# DrivePDU.net
KiCad netlist of a schematic drawn in EAGLE
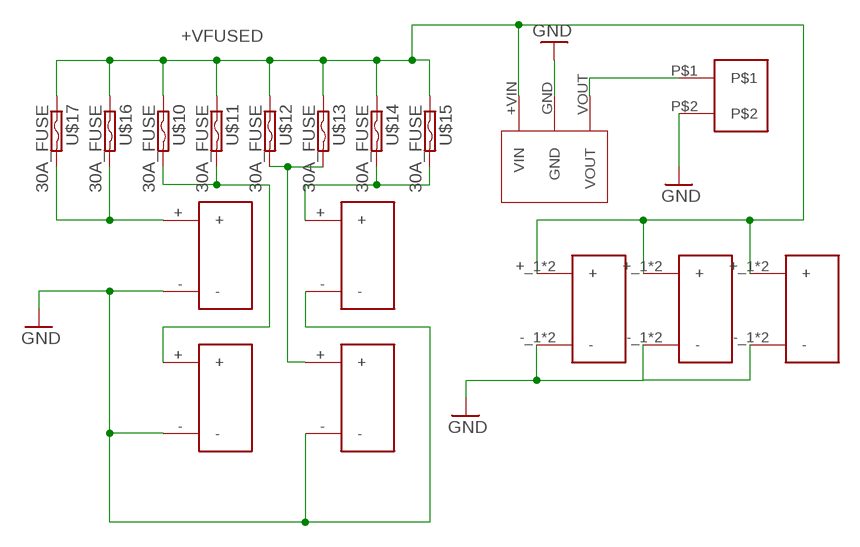
[diagram p0: schematic, sheet 1]

(export (version "E")
  (design (tool "Eeschema 10.0.6"))
  (components
    (comp (ref "U$1")
      (value "PP45_HOR_4GRD")
      (footprint "eagle-import:PP45_HOR_4GRD")
      (libsource (lib "eagle-import") (part "PP45_HOR_4GRD"))
    )
    (comp (ref "U$2")
      (value "PP45_HOR_4GRD")
      (footprint "eagle-import:PP45_HOR_4GRD")
      (libsource (lib "eagle-import") (part "PP45_HOR_4GRD"))
    )
    (comp (ref "U$3")
      (value "PP45_HOR_4GRD")
      (footprint "eagle-import:PP45_HOR_4GRD")
      (libsource (lib "eagle-import") (part "PP45_HOR_4GRD"))
    )
    (comp (ref "U$4")
      (value "PP45_HOR_2BOT")
      (footprint "eagle-import:PP45_HOR_2BOT")
      (libsource (lib "eagle-import") (part "PP45_HOR_2BOT"))
    )
    (comp (ref "U$5")
      (value "PP45_HOR_2BOT")
      (footprint "eagle-import:PP45_HOR_2BOT")
      (libsource (lib "eagle-import") (part "PP45_HOR_2BOT"))
    )
    (comp (ref "U$6")
      (value "PP45_HOR_2BOT")
      (footprint "eagle-import:PP45_HOR_2BOT")
      (libsource (lib "eagle-import") (part "PP45_HOR_2BOT"))
    )
    (comp (ref "U$7")
      (value "PP45_HOR_2BOT")
      (footprint "eagle-import:PP45_HOR_2BOT")
      (libsource (lib "eagle-import") (part "PP45_HOR_2BOT"))
    )
    (comp (ref "U$8")
      (value "AMP-MTE-2MALE")
      (footprint "eagle-import:AMP-MTE-2MALE")
      (libsource (lib "eagle-import") (part "AMP-MTE-2MALE"))
    )
    (comp (ref "U$9")
      (value "R-78E3.3-0.5")
      (footprint "eagle-import:R-78E3.3-0.5")
      (libsource (lib "eagle-import") (part "R-78E3.3-0.5"))
    )
    (comp (ref "U$10")
      (value "30A_FUSE")
      (footprint "eagle-import:01220090Z")
      (libsource (lib "eagle-import") (part "30A_FUSE"))
    )
    (comp (ref "U$11")
      (value "30A_FUSE")
      (footprint "eagle-import:01220090Z")
      (libsource (lib "eagle-import") (part "30A_FUSE"))
    )
    (comp (ref "U$12")
      (value "30A_FUSE")
      (footprint "eagle-import:01220090Z")
      (libsource (lib "eagle-import") (part "30A_FUSE"))
    )
    (comp (ref "U$13")
      (value "30A_FUSE")
      (footprint "eagle-import:01220090Z")
      (libsource (lib "eagle-import") (part "30A_FUSE"))
    )
    (comp (ref "U$14")
      (value "30A_FUSE")
      (footprint "eagle-import:01220090Z")
      (libsource (lib "eagle-import") (part "30A_FUSE"))
    )
    (comp (ref "U$15")
      (value "30A_FUSE")
      (footprint "eagle-import:01220090Z")
      (libsource (lib "eagle-import") (part "30A_FUSE"))
    )
    (comp (ref "U$16")
      (value "30A_FUSE")
      (footprint "eagle-import:01220090Z")
      (libsource (lib "eagle-import") (part "30A_FUSE"))
    )
    (comp (ref "U$17")
      (value "30A_FUSE")
      (footprint "eagle-import:01220090Z")
      (libsource (lib "eagle-import") (part "30A_FUSE"))
    )
  )
  (nets
    (net (code "1") (name "/+VFUSED") (class "Default")
      (node (ref "U$1") (pin "+_1") (pinfunction "+_+_1") (pintype "bidirectional"))
      (node (ref "U$1") (pin "+_2") (pinfunction "+_+_2") (pintype "bidirectional"))
      (node (ref "U$10") (pin "P$1") (pinfunction "1_P$1") (pintype "passive"))
      (node (ref "U$10") (pin "P$2") (pinfunction "1_P$2") (pintype "passive"))
      (node (ref "U$11") (pin "P$1") (pinfunction "1_P$1") (pintype "passive"))
      (node (ref "U$11") (pin "P$2") (pinfunction "1_P$2") (pintype "passive"))
      (node (ref "U$12") (pin "P$1") (pinfunction "1_P$1") (pintype "passive"))
      (node (ref "U$12") (pin "P$2") (pinfunction "1_P$2") (pintype "passive"))
      (node (ref "U$13") (pin "P$1") (pinfunction "1_P$1") (pintype "passive"))
      (node (ref "U$13") (pin "P$2") (pinfunction "1_P$2") (pintype "passive"))
      (node (ref "U$14") (pin "P$1") (pinfunction "1_P$1") (pintype "passive"))
      (node (ref "U$14") (pin "P$2") (pinfunction "1_P$2") (pintype "passive"))
      (node (ref "U$15") (pin "P$1") (pinfunction "1_P$1") (pintype "passive"))
      (node (ref "U$15") (pin "P$2") (pinfunction "1_P$2") (pintype "passive"))
      (node (ref "U$16") (pin "P$1") (pinfunction "1_P$1") (pintype "passive"))
      (node (ref "U$16") (pin "P$2") (pinfunction "1_P$2") (pintype "passive"))
      (node (ref "U$17") (pin "P$1") (pinfunction "1_P$1") (pintype "passive"))
      (node (ref "U$17") (pin "P$2") (pinfunction "1_P$2") (pintype "passive"))
      (node (ref "U$2") (pin "+_1") (pinfunction "+_+_1") (pintype "bidirectional"))
      (node (ref "U$2") (pin "+_2") (pinfunction "+_+_2") (pintype "bidirectional"))
      (node (ref "U$3") (pin "+_1") (pinfunction "+_+_1") (pintype "bidirectional"))
      (node (ref "U$3") (pin "+_2") (pinfunction "+_+_2") (pintype "bidirectional"))
      (node (ref "U$9") (pin "+VIN") (pinfunction "VIN_+VIN") (pintype "bidirectional"))
    )
    (net (code "2") (name "GND") (class "Default")
      (node (ref "U$1") (pin "-_1") (pinfunction "-_-_1") (pintype "bidirectional"))
      (node (ref "U$1") (pin "-_2") (pinfunction "-_-_2") (pintype "bidirectional"))
      (node (ref "U$2") (pin "-_1") (pinfunction "-_-_1") (pintype "bidirectional"))
      (node (ref "U$2") (pin "-_2") (pinfunction "-_-_2") (pintype "bidirectional"))
      (node (ref "U$3") (pin "-_1") (pinfunction "-_-_1") (pintype "bidirectional"))
      (node (ref "U$3") (pin "-_2") (pinfunction "-_-_2") (pintype "bidirectional"))
      (node (ref "U$4") (pin "-") (pinfunction "-_-") (pintype "bidirectional"))
      (node (ref "U$5") (pin "-") (pinfunction "-_-") (pintype "bidirectional"))
      (node (ref "U$6") (pin "-") (pinfunction "-_-") (pintype "bidirectional"))
      (node (ref "U$7") (pin "-") (pinfunction "-_-") (pintype "bidirectional"))
      (node (ref "U$8") (pin "P$2") (pinfunction "P$2_P$2") (pintype "bidirectional"))
      (node (ref "U$9") (pin "GND") (pinfunction "GND_GND") (pintype "bidirectional"))
    )
    (net (code "3") (name "Net-(U$8-PadP$1)") (class "Default")
      (node (ref "U$8") (pin "P$1") (pinfunction "P$1_P$1") (pintype "bidirectional"))
      (node (ref "U$9") (pin "VOUT") (pinfunction "VOUT_VOUT") (pintype "bidirectional"))
    )
    (net (code "4") (name "Net-(U$10-2-PadP$3)") (class "Default")
      (node (ref "U$10") (pin "P$3") (pinfunction "2_P$3") (pintype "passive"))
      (node (ref "U$10") (pin "P$4") (pinfunction "2_P$4") (pintype "passive"))
      (node (ref "U$11") (pin "P$3") (pinfunction "2_P$3") (pintype "passive"))
      (node (ref "U$11") (pin "P$4") (pinfunction "2_P$4") (pintype "passive"))
      (node (ref "U$4") (pin "+") (pinfunction "+_+") (pintype "bidirectional"))
    )
    (net (code "5") (name "Net-(U$12-2-PadP$3)") (class "Default")
      (node (ref "U$12") (pin "P$3") (pinfunction "2_P$3") (pintype "passive"))
      (node (ref "U$12") (pin "P$4") (pinfunction "2_P$4") (pintype "passive"))
      (node (ref "U$13") (pin "P$3") (pinfunction "2_P$3") (pintype "passive"))
      (node (ref "U$13") (pin "P$4") (pinfunction "2_P$4") (pintype "passive"))
      (node (ref "U$6") (pin "+") (pinfunction "+_+") (pintype "bidirectional"))
    )
    (net (code "6") (name "Net-(U$14-2-PadP$3)") (class "Default")
      (node (ref "U$14") (pin "P$3") (pinfunction "2_P$3") (pintype "passive"))
      (node (ref "U$14") (pin "P$4") (pinfunction "2_P$4") (pintype "passive"))
      (node (ref "U$15") (pin "P$3") (pinfunction "2_P$3") (pintype "passive"))
      (node (ref "U$15") (pin "P$4") (pinfunction "2_P$4") (pintype "passive"))
      (node (ref "U$5") (pin "+") (pinfunction "+_+") (pintype "bidirectional"))
    )
    (net (code "7") (name "Net-(U$16-2-PadP$3)") (class "Default")
      (node (ref "U$16") (pin "P$3") (pinfunction "2_P$3") (pintype "passive"))
      (node (ref "U$16") (pin "P$4") (pinfunction "2_P$4") (pintype "passive"))
      (node (ref "U$17") (pin "P$3") (pinfunction "2_P$3") (pintype "passive"))
      (node (ref "U$17") (pin "P$4") (pinfunction "2_P$4") (pintype "passive"))
      (node (ref "U$7") (pin "+") (pinfunction "+_+") (pintype "bidirectional"))
    )
  )
)
